# bbf-eurojacks.net
KiCad netlist of a schematic drawn in EAGLE
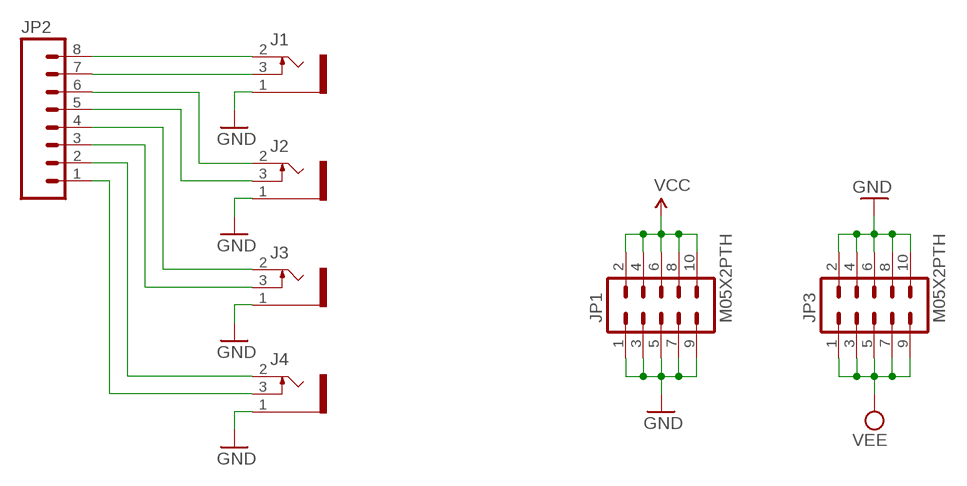
[diagram p0: schematic, sheet 1]

(export (version "E")
  (design (tool "Eeschema 10.0.6"))
  (components
    (comp (ref "J1")
      (value "1502_03SLOTTED")
      (footprint "eagle-import:1502_03_SLOTTED")
      (libsource (lib "eagle-import") (part "1502_03SLOTTED"))
    )
    (comp (ref "J2")
      (value "1502_03SLOTTED")
      (footprint "eagle-import:1502_03_SLOTTED")
      (libsource (lib "eagle-import") (part "1502_03SLOTTED"))
    )
    (comp (ref "J3")
      (value "1502_03SLOTTED")
      (footprint "eagle-import:1502_03_SLOTTED")
      (libsource (lib "eagle-import") (part "1502_03SLOTTED"))
    )
    (comp (ref "J4")
      (value "1502_03SLOTTED")
      (footprint "eagle-import:1502_03_SLOTTED")
      (libsource (lib "eagle-import") (part "1502_03SLOTTED"))
    )
    (comp (ref "JP1")
      (value "M05X2PTH")
      (footprint "eagle-import:AVR_ICSP")
      (libsource (lib "eagle-import") (part "M05X2PTH"))
    )
    (comp (ref "JP2")
      (value "M08")
      (footprint "eagle-import:1X08")
      (libsource (lib "eagle-import") (part "M08"))
    )
    (comp (ref "JP3")
      (value "M05X2PTH")
      (footprint "eagle-import:AVR_ICSP")
      (libsource (lib "eagle-import") (part "M05X2PTH"))
    )
  )
  (nets
    (net (code "1") (name "GND") (class "Default")
      (node (ref "J1") (pin "1") (pinfunction "1_1") (pintype "passive"))
      (node (ref "J2") (pin "1") (pinfunction "1_1") (pintype "passive"))
      (node (ref "J3") (pin "1") (pinfunction "1_1") (pintype "passive"))
      (node (ref "J4") (pin "1") (pinfunction "1_1") (pintype "passive"))
      (node (ref "JP1") (pin "1") (pinfunction "1_1") (pintype "passive"))
      (node (ref "JP1") (pin "3") (pinfunction "3_3") (pintype "passive"))
      (node (ref "JP1") (pin "5") (pinfunction "5_5") (pintype "passive"))
      (node (ref "JP1") (pin "7") (pinfunction "7_7") (pintype "passive"))
      (node (ref "JP1") (pin "9") (pinfunction "9_9") (pintype "passive"))
      (node (ref "JP3") (pin "10") (pinfunction "10_10") (pintype "passive"))
      (node (ref "JP3") (pin "2") (pinfunction "2_2") (pintype "passive"))
      (node (ref "JP3") (pin "4") (pinfunction "4_4") (pintype "passive"))
      (node (ref "JP3") (pin "6") (pinfunction "6_6") (pintype "passive"))
      (node (ref "JP3") (pin "8") (pinfunction "8_8") (pintype "passive"))
    )
    (net (code "2") (name "Net-(J1-Pad2)") (class "Default")
      (node (ref "J1") (pin "2") (pinfunction "2_2") (pintype "passive"))
      (node (ref "JP2") (pin "8") (pinfunction "8_8") (pintype "passive"))
    )
    (net (code "3") (name "Net-(J1-Pad3)") (class "Default")
      (node (ref "J1") (pin "3") (pinfunction "3_3") (pintype "passive"))
      (node (ref "JP2") (pin "7") (pinfunction "7_7") (pintype "passive"))
    )
    (net (code "4") (name "Net-(J2-Pad2)") (class "Default")
      (node (ref "J2") (pin "2") (pinfunction "2_2") (pintype "passive"))
      (node (ref "JP2") (pin "6") (pinfunction "6_6") (pintype "passive"))
    )
    (net (code "5") (name "Net-(J2-Pad3)") (class "Default")
      (node (ref "J2") (pin "3") (pinfunction "3_3") (pintype "passive"))
      (node (ref "JP2") (pin "5") (pinfunction "5_5") (pintype "passive"))
    )
    (net (code "6") (name "Net-(J3-Pad2)") (class "Default")
      (node (ref "J3") (pin "2") (pinfunction "2_2") (pintype "passive"))
      (node (ref "JP2") (pin "4") (pinfunction "4_4") (pintype "passive"))
    )
    (net (code "7") (name "Net-(J3-Pad3)") (class "Default")
      (node (ref "J3") (pin "3") (pinfunction "3_3") (pintype "passive"))
      (node (ref "JP2") (pin "3") (pinfunction "3_3") (pintype "passive"))
    )
    (net (code "8") (name "Net-(J4-Pad2)") (class "Default")
      (node (ref "J4") (pin "2") (pinfunction "2_2") (pintype "passive"))
      (node (ref "JP2") (pin "2") (pinfunction "2_2") (pintype "passive"))
    )
    (net (code "9") (name "Net-(J4-Pad3)") (class "Default")
      (node (ref "J4") (pin "3") (pinfunction "3_3") (pintype "passive"))
      (node (ref "JP2") (pin "1") (pinfunction "1_1") (pintype "passive"))
    )
    (net (code "10") (name "VCC") (class "Default")
      (node (ref "JP1") (pin "10") (pinfunction "10_10") (pintype "passive"))
      (node (ref "JP1") (pin "2") (pinfunction "2_2") (pintype "passive"))
      (node (ref "JP1") (pin "4") (pinfunction "4_4") (pintype "passive"))
      (node (ref "JP1") (pin "6") (pinfunction "6_6") (pintype "passive"))
      (node (ref "JP1") (pin "8") (pinfunction "8_8") (pintype "passive"))
    )
    (net (code "11") (name "VEE") (class "Default")
      (node (ref "JP3") (pin "1") (pinfunction "1_1") (pintype "passive"))
      (node (ref "JP3") (pin "3") (pinfunction "3_3") (pintype "passive"))
      (node (ref "JP3") (pin "5") (pinfunction "5_5") (pintype "passive"))
      (node (ref "JP3") (pin "7") (pinfunction "7_7") (pintype "passive"))
      (node (ref "JP3") (pin "9") (pinfunction "9_9") (pintype "passive"))
    )
  )
)
